# ads-b.net
KiCad netlist of a schematic drawn in EAGLE
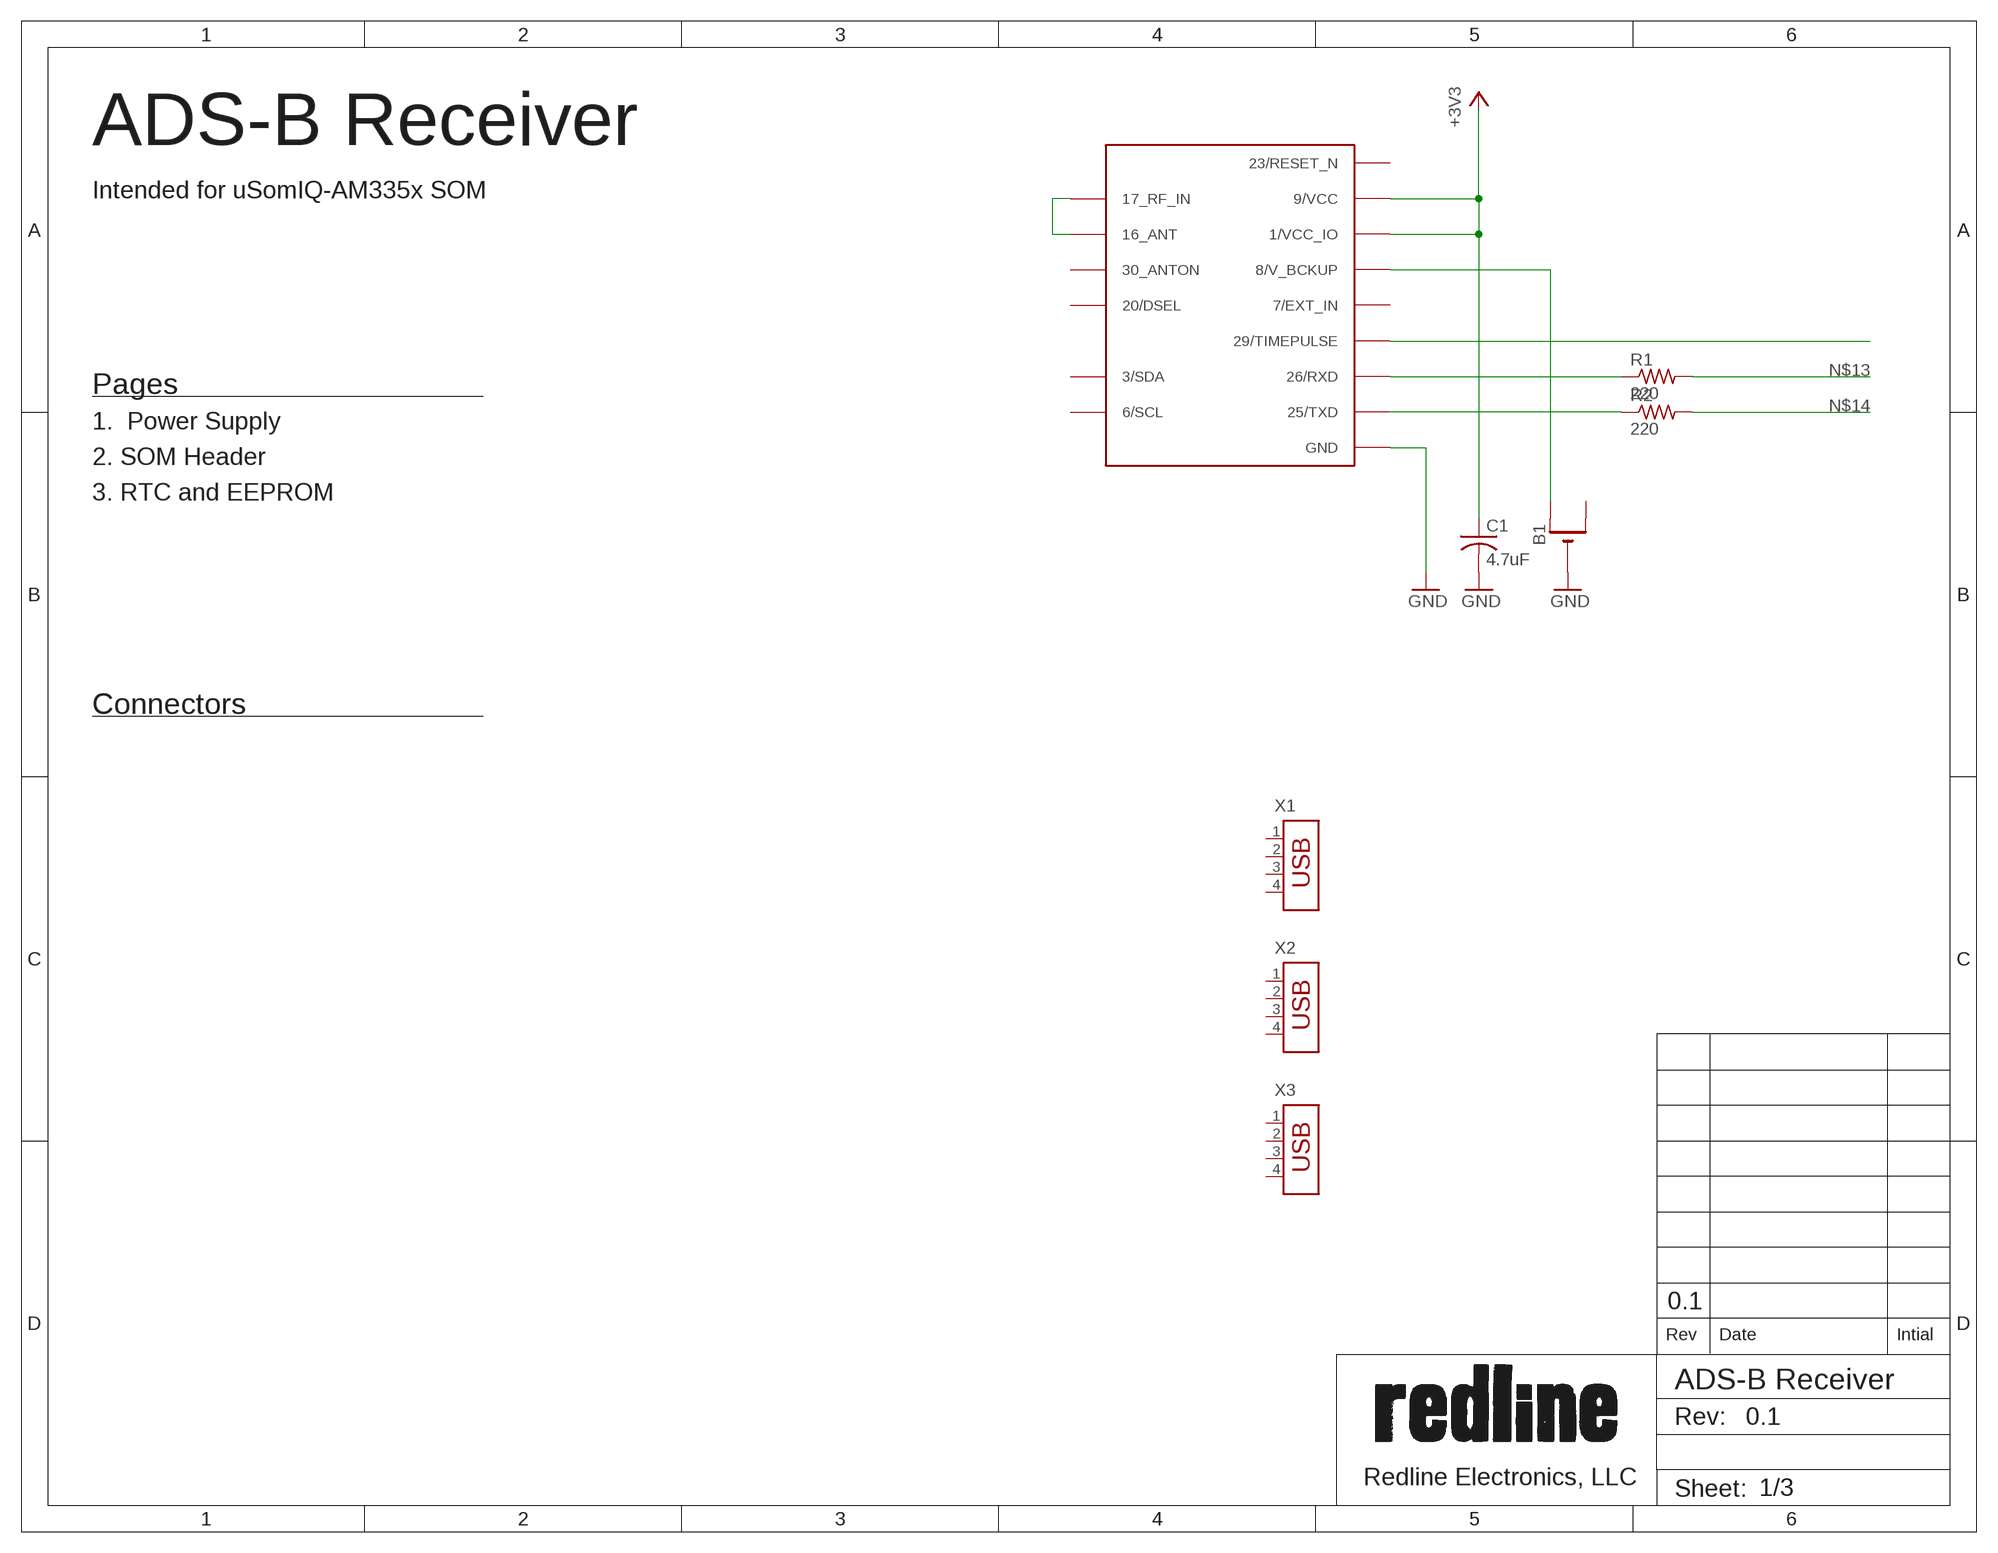
[diagram p0: schematic, sheet 1]
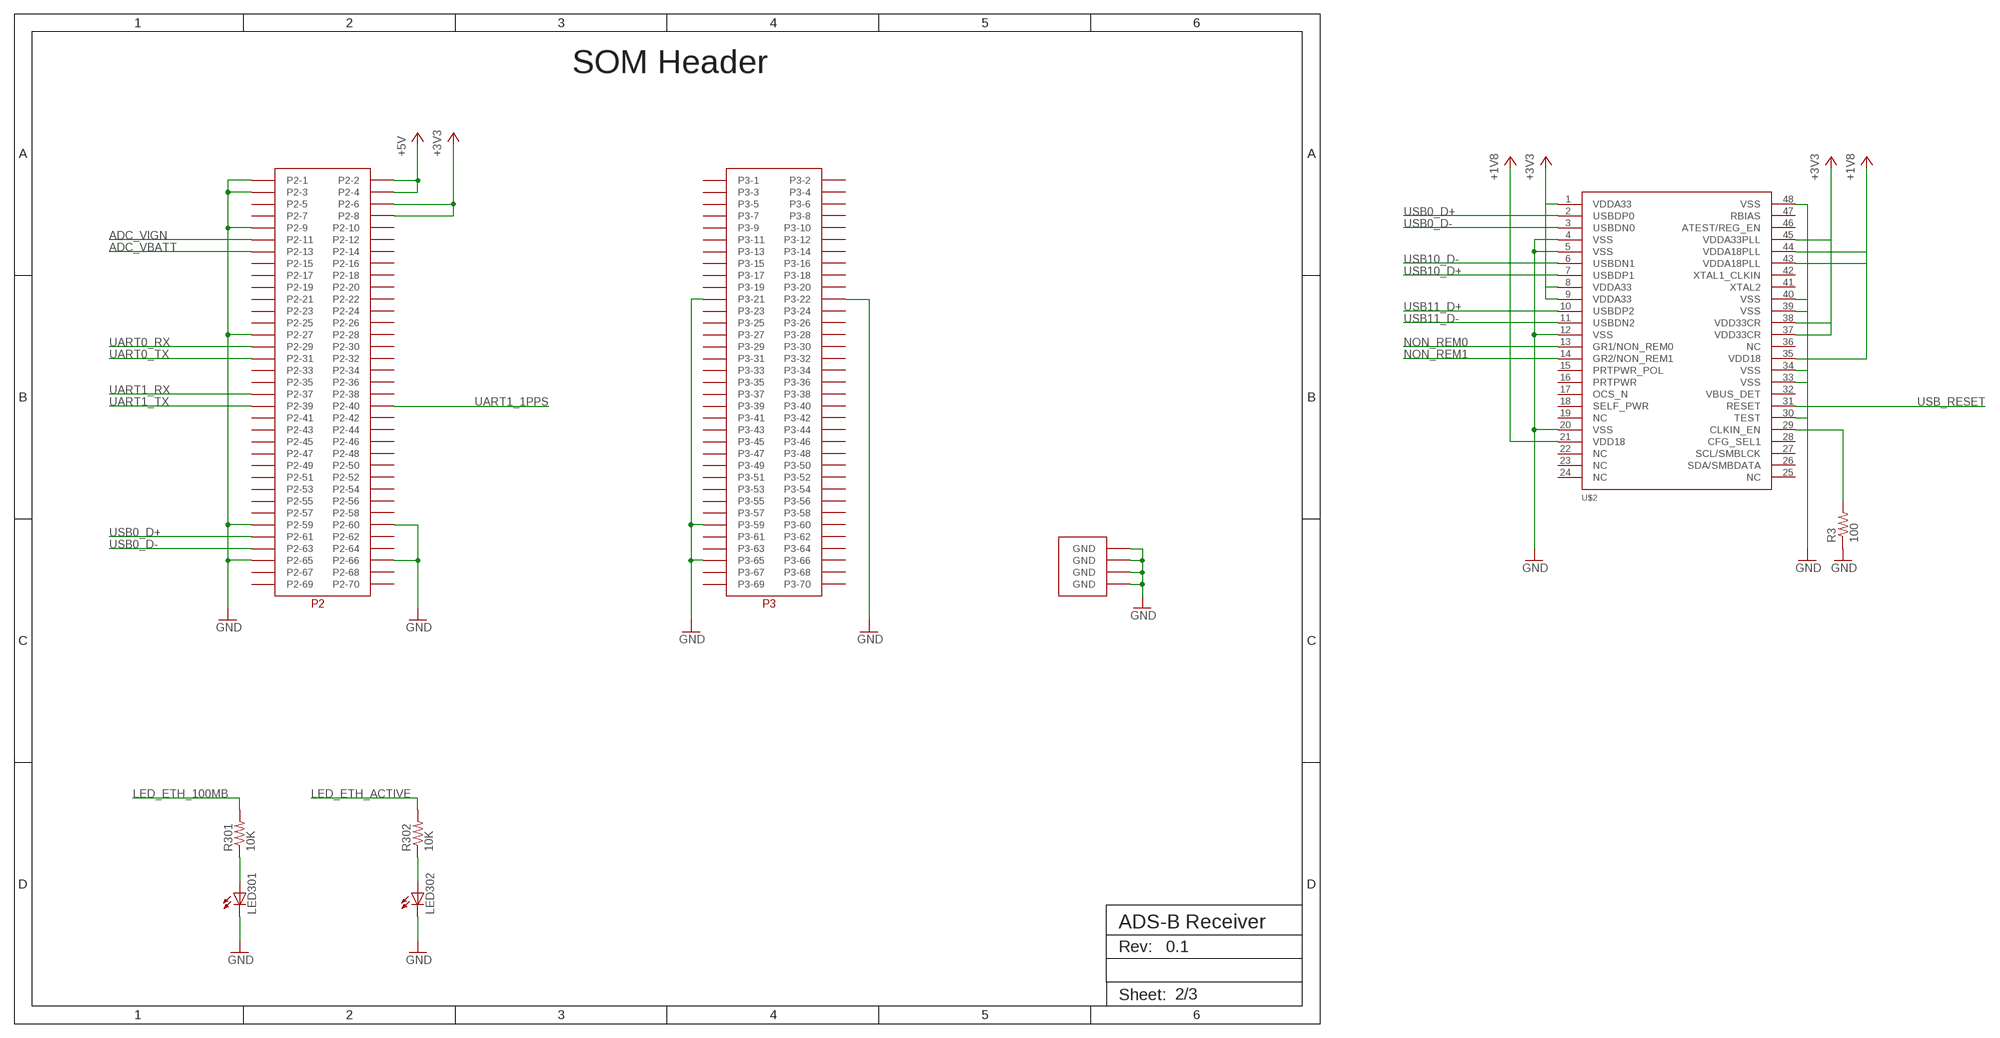
[diagram p1: schematic, sheet 2]
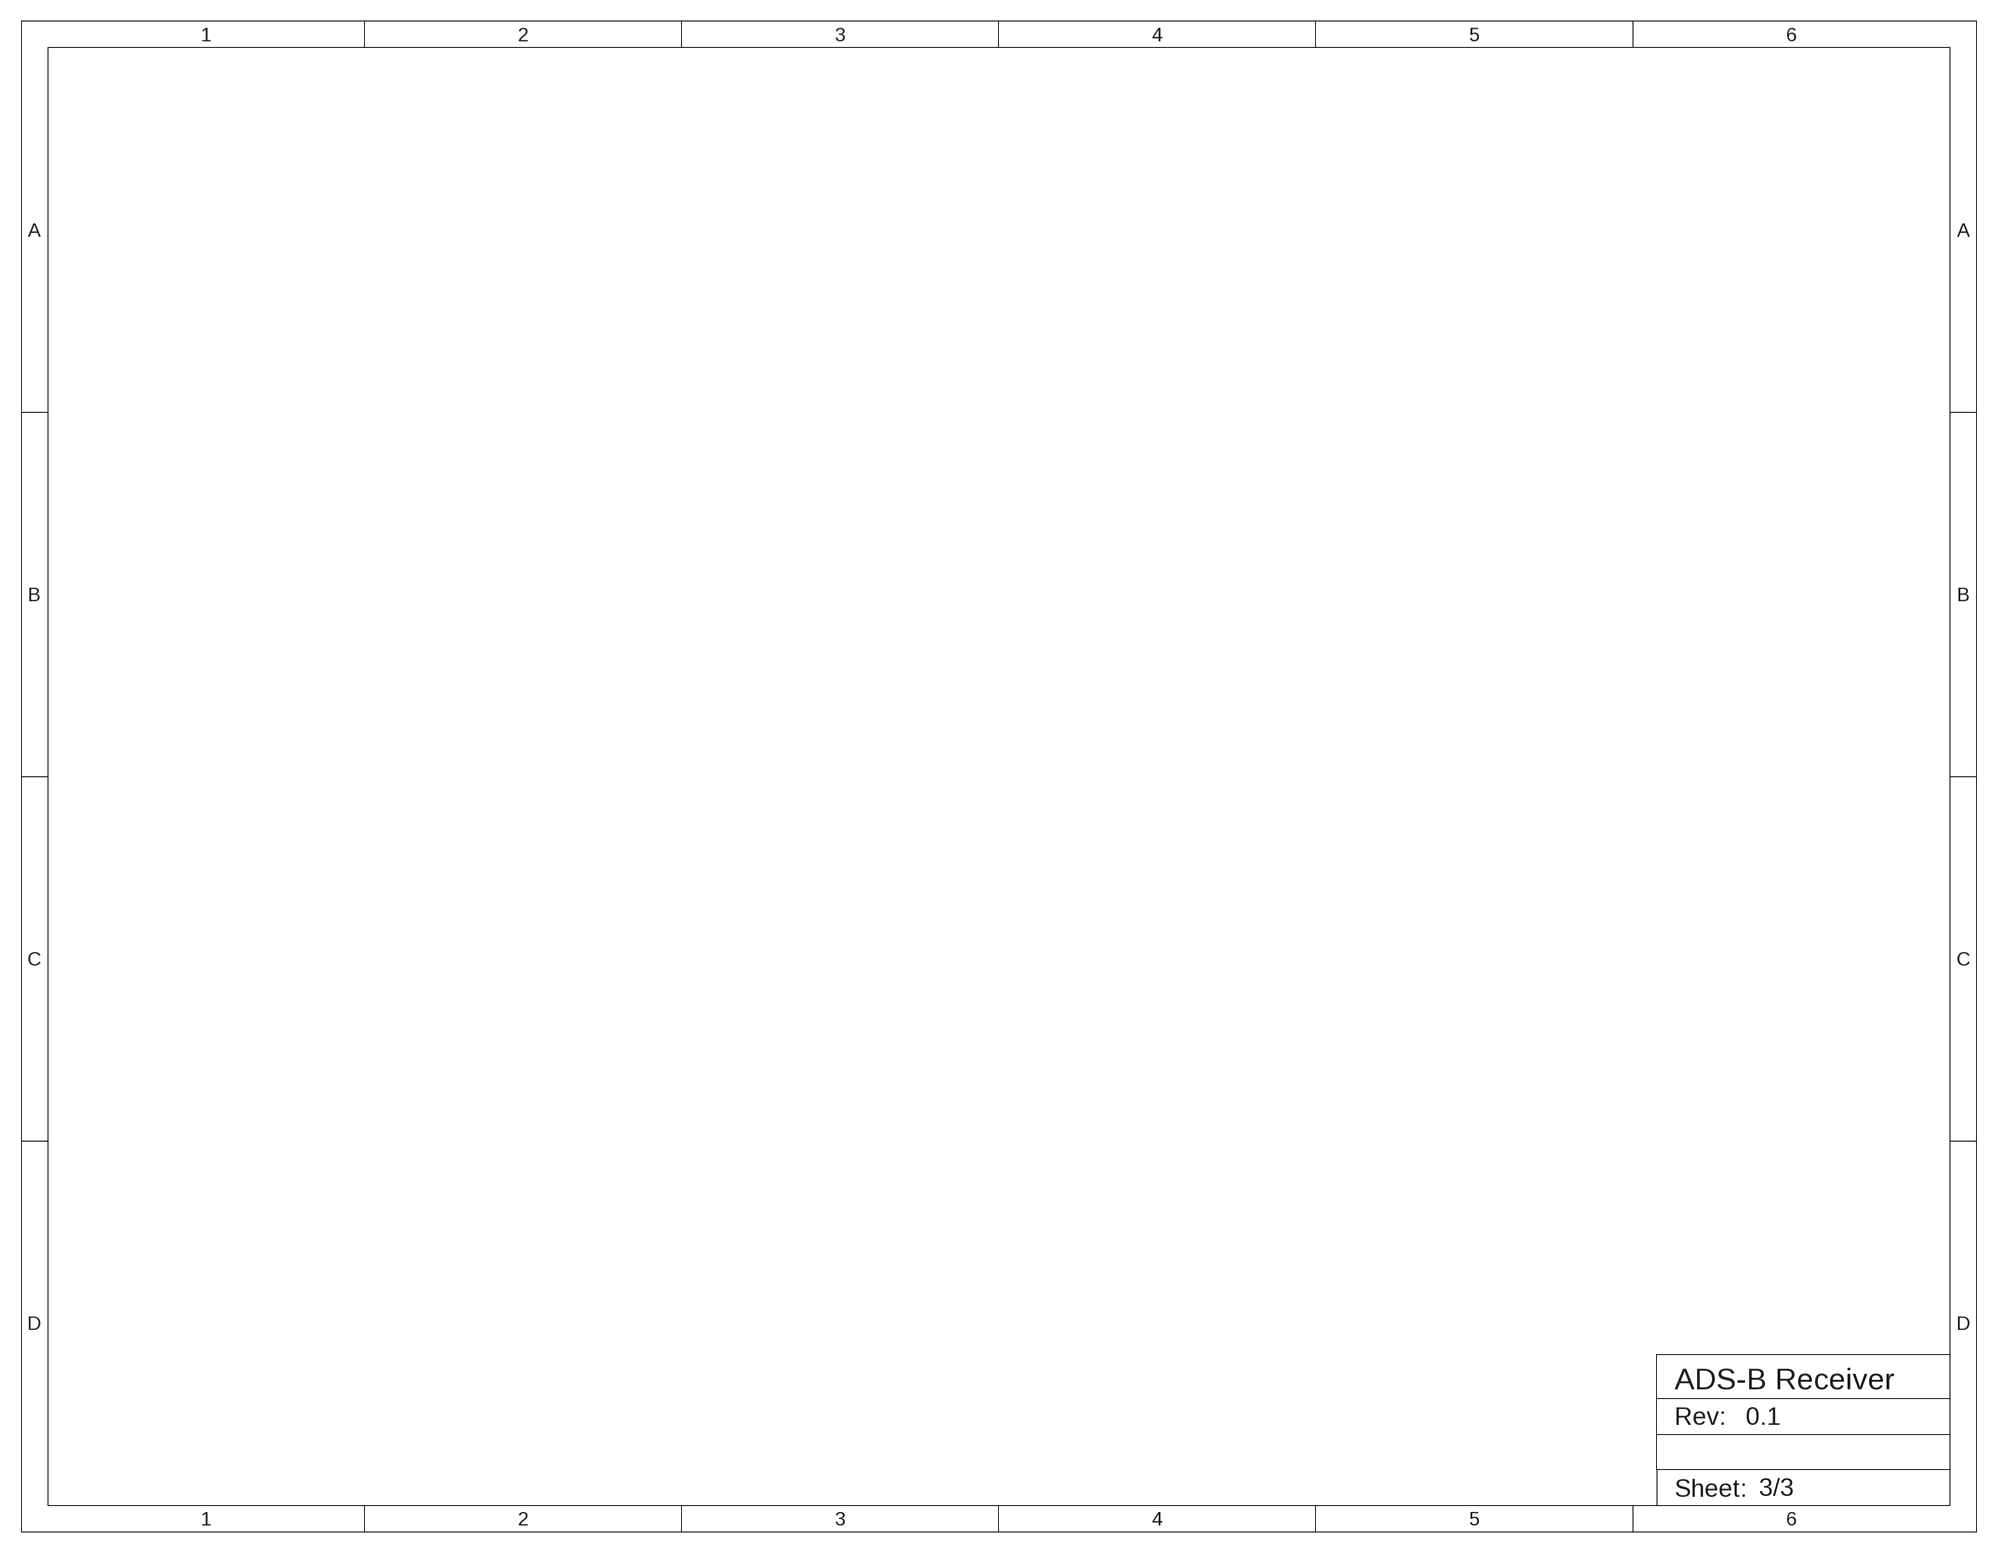
[diagram p2: schematic, sheet 3]

(export (version "E")
  (design (tool "Eeschema 10.0.6"))
  (components
    (comp (ref "LED301")
      (value "LEDSML0603")
      (footprint "eagle-import:SML0603")
      (libsource (lib "eagle-import") (part "LEDSML0603"))
    )
    (comp (ref "LED302")
      (value "LEDSML0603")
      (footprint "eagle-import:SML0603")
      (libsource (lib "eagle-import") (part "LEDSML0603"))
    )
    (comp (ref "P301")
      (value "USOMIQ-AM335X")
      (footprint "eagle-import:USOMIQ-AM335X")
      (libsource (lib "eagle-import") (part "USOMIQ-AM335X"))
    )
    (comp (ref "R3")
      (value "100")
      (footprint "eagle-import:R0603")
      (libsource (lib "eagle-import") (part "R-US_R0603"))
    )
    (comp (ref "R301")
      (value "10K")
      (footprint "eagle-import:R0603")
      (libsource (lib "eagle-import") (part "R-US_R0603"))
    )
    (comp (ref "R302")
      (value "10K")
      (footprint "eagle-import:R0603")
      (libsource (lib "eagle-import") (part "R-US_R0603"))
    )
    (comp (ref "U$2")
      (value "USB2502")
      (footprint "eagle-import:S-PQFP-G48")
      (libsource (lib "eagle-import") (part "USB2502"))
    )
    (comp (ref "B1")
      (value "CR1220SMT")
      (footprint "eagle-import:CR1220-SMD")
      (libsource (lib "eagle-import") (part "CR1220SMT"))
    )
    (comp (ref "C1")
      (value "4.7uF")
      (footprint "eagle-import:C0603")
      (libsource (lib "eagle-import") (part "C-USC0603"))
    )
    (comp (ref "R1")
      (value "220")
      (footprint "eagle-import:R0603")
      (libsource (lib "eagle-import") (part "R-US_R0603"))
    )
    (comp (ref "R2")
      (value "220")
      (footprint "eagle-import:R0603")
      (libsource (lib "eagle-import") (part "R-US_R0603"))
    )
    (comp (ref "U$1")
      (value "UBLOX_CAM")
      (footprint "eagle-import:UBLOX_CAM")
      (libsource (lib "eagle-import") (part "UBLOX_CAM"))
    )
    (comp (ref "X1")
      (value "USB-787616")
      (footprint "eagle-import:USB")
      (libsource (lib "eagle-import") (part "USB-787616"))
    )
    (comp (ref "X2")
      (value "USB-787616")
      (footprint "eagle-import:USB")
      (libsource (lib "eagle-import") (part "USB-787616"))
    )
    (comp (ref "X3")
      (value "USB-787616")
      (footprint "eagle-import:USB")
      (libsource (lib "eagle-import") (part "USB-787616"))
    )
  )
  (nets
    (net (code "1") (name "+3V3") (class "Default")
      (node (ref "C1") (pin "1") (pinfunction "1_1") (pintype "passive"))
      (node (ref "P301") (pin "P$6") (pinfunction "P2-6_P$6") (pintype "bidirectional"))
      (node (ref "P301") (pin "P$8") (pinfunction "P2-8_P$8") (pintype "bidirectional"))
      (node (ref "U$1") (pin "1/VCC_IO") (pinfunction "1/VCC_IO_1/VCC_IO") (pintype "power_in"))
      (node (ref "U$1") (pin "9/VCC") (pinfunction "9/VCC_9/VCC") (pintype "power_in"))
      (node (ref "U$2") (pin "1") (pinfunction "VDDA33_1") (pintype "bidirectional"))
      (node (ref "U$2") (pin "21") (pinfunction "VDD18_21") (pintype "bidirectional"))
      (node (ref "U$2") (pin "35") (pinfunction "VDD18_35") (pintype "bidirectional"))
      (node (ref "U$2") (pin "37") (pinfunction "VDD33CR_37") (pintype "bidirectional"))
      (node (ref "U$2") (pin "38") (pinfunction "VDD33CR_38") (pintype "bidirectional"))
      (node (ref "U$2") (pin "43") (pinfunction "VDDA18PLL_43") (pintype "bidirectional"))
      (node (ref "U$2") (pin "44") (pinfunction "VDDA18PLL_44") (pintype "bidirectional"))
      (node (ref "U$2") (pin "45") (pinfunction "VDDA33PLL_45") (pintype "bidirectional"))
      (node (ref "U$2") (pin "8") (pinfunction "VDDA33_8") (pintype "bidirectional"))
      (node (ref "U$2") (pin "9") (pinfunction "VDDA33_9") (pintype "bidirectional"))
    )
    (net (code "2") (name "+5V") (class "Default")
      (node (ref "P301") (pin "P$2") (pinfunction "P2-2_P$2") (pintype "bidirectional"))
      (node (ref "P301") (pin "P$4") (pinfunction "P2-4_P$4") (pintype "bidirectional"))
    )
    (net (code "3") (name "23{slash}RESET_N") (class "Default")
      (node (ref "U$1") (pin "23/RESET_N") (pinfunction "23/RESET_N_23/RESET_N") (pintype "power_in"))
    )
    (net (code "4") (name "ADC_VBATT") (class "Default")
      (node (ref "P301") (pin "P$13") (pinfunction "P2-13_P$13") (pintype "bidirectional"))
    )
    (net (code "5") (name "ADC_VIGN") (class "Default")
      (node (ref "P301") (pin "P$11") (pinfunction "P2-11_P$11") (pintype "bidirectional"))
    )
    (net (code "6") (name "GND") (class "Default")
      (node (ref "B1") (pin "-") (pinfunction "-_-") (pintype "passive"))
      (node (ref "C1") (pin "2") (pinfunction "2_2") (pintype "passive"))
      (node (ref "LED301") (pin "C") (pinfunction "C_C") (pintype "passive"))
      (node (ref "LED302") (pin "C") (pinfunction "C_C") (pintype "passive"))
      (node (ref "P301") (pin "MOUNT@0") (pinfunction "GND_MOUNT@0") (pintype "bidirectional"))
      (node (ref "P301") (pin "MOUNT@1") (pinfunction "GND_MOUNT@1") (pintype "bidirectional"))
      (node (ref "P301") (pin "MOUNT@2") (pinfunction "GND_MOUNT@2") (pintype "bidirectional"))
      (node (ref "P301") (pin "MOUNT@3") (pinfunction "GND_MOUNT@3") (pintype "bidirectional"))
      (node (ref "P301") (pin "P$1") (pinfunction "P2-1_P$1") (pintype "bidirectional"))
      (node (ref "P301") (pin "P$129") (pinfunction "P3-59_P$129") (pintype "bidirectional"))
      (node (ref "P301") (pin "P$135") (pinfunction "P3-65_P$135") (pintype "bidirectional"))
      (node (ref "P301") (pin "P$27") (pinfunction "P2-27_P$27") (pintype "bidirectional"))
      (node (ref "P301") (pin "P$3") (pinfunction "P2-3_P$3") (pintype "bidirectional"))
      (node (ref "P301") (pin "P$59") (pinfunction "P2-59_P$59") (pintype "bidirectional"))
      (node (ref "P301") (pin "P$60") (pinfunction "P2-60_P$60") (pintype "bidirectional"))
      (node (ref "P301") (pin "P$65") (pinfunction "P2-65_P$65") (pintype "bidirectional"))
      (node (ref "P301") (pin "P$66") (pinfunction "P2-66_P$66") (pintype "bidirectional"))
      (node (ref "P301") (pin "P$9") (pinfunction "P2-9_P$9") (pintype "bidirectional"))
      (node (ref "P301") (pin "P$91") (pinfunction "P3-21_P$91") (pintype "bidirectional"))
      (node (ref "P301") (pin "P$92") (pinfunction "P3-22_P$92") (pintype "bidirectional"))
      (node (ref "R3") (pin "1") (pinfunction "1_1") (pintype "passive"))
      (node (ref "U$1") (pin "10/GND") (pinfunction "GND_10/GND") (pintype "power_in"))
      (node (ref "U$1") (pin "11/GND") (pinfunction "GND_11/GND") (pintype "power_in"))
      (node (ref "U$1") (pin "12/GND") (pinfunction "GND_12/GND") (pintype "power_in"))
      (node (ref "U$1") (pin "13/GND") (pinfunction "GND_13/GND") (pintype "power_in"))
      (node (ref "U$1") (pin "14/GND") (pinfunction "GND_14/GND") (pintype "power_in"))
      (node (ref "U$1") (pin "15/GND") (pinfunction "GND_15/GND") (pintype "power_in"))
      (node (ref "U$1") (pin "18/GND") (pinfunction "GND_18/GND") (pintype "power_in"))
      (node (ref "U$1") (pin "19/GND") (pinfunction "GND_19/GND") (pintype "power_in"))
      (node (ref "U$1") (pin "21/GND") (pinfunction "GND_21/GND") (pintype "power_in"))
      (node (ref "U$1") (pin "22/GND") (pinfunction "GND_22/GND") (pintype "power_in"))
      (node (ref "U$1") (pin "27/GND") (pinfunction "GND_27/GND") (pintype "power_in"))
      (node (ref "U$1") (pin "31/GND") (pinfunction "GND_31/GND") (pintype "power_in"))
      (node (ref "U$1") (pin "4/GND") (pinfunction "GND_4/GND") (pintype "power_in"))
      (node (ref "U$1") (pin "5/GND") (pinfunction "GND_5/GND") (pintype "power_in"))
      (node (ref "U$2") (pin "12") (pinfunction "VSS_12") (pintype "bidirectional"))
      (node (ref "U$2") (pin "20") (pinfunction "VSS_20") (pintype "bidirectional"))
      (node (ref "U$2") (pin "30") (pinfunction "TEST_30") (pintype "bidirectional"))
      (node (ref "U$2") (pin "33") (pinfunction "VSS_33") (pintype "bidirectional"))
      (node (ref "U$2") (pin "34") (pinfunction "VSS_34") (pintype "bidirectional"))
      (node (ref "U$2") (pin "39") (pinfunction "VSS_39") (pintype "bidirectional"))
      (node (ref "U$2") (pin "4") (pinfunction "VSS_4") (pintype "bidirectional"))
      (node (ref "U$2") (pin "40") (pinfunction "VSS_40") (pintype "bidirectional"))
      (node (ref "U$2") (pin "48") (pinfunction "VSS_48") (pintype "bidirectional"))
      (node (ref "U$2") (pin "5") (pinfunction "VSS_5") (pintype "bidirectional"))
    )
    (net (code "7") (name "LED_ETH_100MB") (class "Default")
      (node (ref "R301") (pin "2") (pinfunction "2_2") (pintype "passive"))
    )
    (net (code "8") (name "LED_ETH_ACTIVE") (class "Default")
      (node (ref "R302") (pin "2") (pinfunction "2_2") (pintype "passive"))
    )
    (net (code "9") (name "N$13") (class "Default")
      (node (ref "R1") (pin "2") (pinfunction "2_2") (pintype "passive"))
    )
    (net (code "10") (name "N$14") (class "Default")
      (node (ref "R2") (pin "2") (pinfunction "2_2") (pintype "passive"))
    )
    (net (code "11") (name "NON_REM0") (class "Default")
      (node (ref "U$2") (pin "13") (pinfunction "GR1/NON_REM0_13") (pintype "bidirectional"))
    )
    (net (code "12") (name "NON_REM1") (class "Default")
      (node (ref "U$2") (pin "14") (pinfunction "GR2/NON_REM1_14") (pintype "bidirectional"))
    )
    (net (code "13") (name "Net-(B1-+)") (class "Default")
      (node (ref "B1") (pin "+$1") (pinfunction "+_+$1") (pintype "passive"))
      (node (ref "U$1") (pin "8/V_BCKP") (pinfunction "8/V_BCKUP_8/V_BCKP") (pintype "bidirectional"))
    )
    (net (code "14") (name "Net-(LED301-PadA)") (class "Default")
      (node (ref "LED301") (pin "A") (pinfunction "A_A") (pintype "passive"))
      (node (ref "R301") (pin "1") (pinfunction "1_1") (pintype "passive"))
    )
    (net (code "15") (name "Net-(LED302-PadA)") (class "Default")
      (node (ref "LED302") (pin "A") (pinfunction "A_A") (pintype "passive"))
      (node (ref "R302") (pin "1") (pinfunction "1_1") (pintype "passive"))
    )
    (net (code "16") (name "Net-(R1-Pad1)") (class "Default")
      (node (ref "R1") (pin "1") (pinfunction "1_1") (pintype "passive"))
      (node (ref "U$1") (pin "26/RXD") (pinfunction "26/RXD_26/RXD") (pintype "bidirectional"))
    )
    (net (code "17") (name "Net-(R2-Pad1)") (class "Default")
      (node (ref "R2") (pin "1") (pinfunction "1_1") (pintype "passive"))
      (node (ref "U$1") (pin "25/TXD") (pinfunction "25/TXD_25/TXD") (pintype "bidirectional"))
    )
    (net (code "18") (name "Net-(U$1-16_ANT)") (class "Default")
      (node (ref "U$1") (pin "16/ANT") (pinfunction "16_ANT_16/ANT") (pintype "power_in"))
      (node (ref "U$1") (pin "17/RF_IN") (pinfunction "17_RF_IN_17/RF_IN") (pintype "bidirectional"))
    )
    (net (code "19") (name "Net-(U$2-CLKIN_EN)") (class "Default")
      (node (ref "R3") (pin "2") (pinfunction "2_2") (pintype "passive"))
      (node (ref "U$2") (pin "29") (pinfunction "CLKIN_EN_29") (pintype "bidirectional"))
    )
    (net (code "20") (name "UART0_RX") (class "Default")
      (node (ref "P301") (pin "P$29") (pinfunction "P2-29_P$29") (pintype "bidirectional"))
    )
    (net (code "21") (name "UART0_TX") (class "Default")
      (node (ref "P301") (pin "P$31") (pinfunction "P2-31_P$31") (pintype "bidirectional"))
    )
    (net (code "22") (name "UART1_1PPS") (class "Default")
      (node (ref "P301") (pin "P$40") (pinfunction "P2-40_P$40") (pintype "bidirectional"))
    )
    (net (code "23") (name "UART1_RX") (class "Default")
      (node (ref "P301") (pin "P$37") (pinfunction "P2-37_P$37") (pintype "bidirectional"))
    )
    (net (code "24") (name "UART1_TX") (class "Default")
      (node (ref "P301") (pin "P$39") (pinfunction "P2-39_P$39") (pintype "bidirectional"))
    )
    (net (code "25") (name "USB0_D+") (class "Default")
      (node (ref "P301") (pin "P$61") (pinfunction "P2-61_P$61") (pintype "bidirectional"))
      (node (ref "U$2") (pin "2") (pinfunction "USBDP0_2") (pintype "bidirectional"))
    )
    (net (code "26") (name "USB0_D-") (class "Default")
      (node (ref "P301") (pin "P$63") (pinfunction "P2-63_P$63") (pintype "bidirectional"))
      (node (ref "U$2") (pin "3") (pinfunction "USBDN0_3") (pintype "bidirectional"))
    )
    (net (code "27") (name "USB10_D+") (class "Default")
      (node (ref "U$2") (pin "7") (pinfunction "USBDP1_7") (pintype "bidirectional"))
    )
    (net (code "28") (name "USB10_D-") (class "Default")
      (node (ref "U$2") (pin "6") (pinfunction "USBDN1_6") (pintype "bidirectional"))
    )
    (net (code "29") (name "USB11_D+") (class "Default")
      (node (ref "U$2") (pin "10") (pinfunction "USBDP2_10") (pintype "bidirectional"))
    )
    (net (code "30") (name "USB11_D-") (class "Default")
      (node (ref "U$2") (pin "11") (pinfunction "USBDN2_11") (pintype "bidirectional"))
    )
    (net (code "31") (name "USB_RESET") (class "Default")
      (node (ref "U$2") (pin "31") (pinfunction "RESET_31") (pintype "bidirectional"))
    )
    (net (code "32") (name "unconnected-(B1-+1-Pad+$2)") (class "Default")
      (node (ref "B1") (pin "+$2") (pinfunction "+1_+$2") (pintype "passive"))
    )
    (net (code "33") (name "unconnected-(P301-P2-5-PadP$5)") (class "Default")
      (node (ref "P301") (pin "P$5") (pinfunction "P2-5_P$5") (pintype "bidirectional"))
    )
    (net (code "34") (name "unconnected-(P301-P2-7-PadP$7)") (class "Default")
      (node (ref "P301") (pin "P$7") (pinfunction "P2-7_P$7") (pintype "bidirectional"))
    )
    (net (code "35") (name "unconnected-(P301-P2-10-PadP$10)") (class "Default")
      (node (ref "P301") (pin "P$10") (pinfunction "P2-10_P$10") (pintype "bidirectional"))
    )
    (net (code "36") (name "unconnected-(P301-P2-12-PadP$12)") (class "Default")
      (node (ref "P301") (pin "P$12") (pinfunction "P2-12_P$12") (pintype "bidirectional"))
    )
    (net (code "37") (name "unconnected-(P301-P2-14-PadP$14)") (class "Default")
      (node (ref "P301") (pin "P$14") (pinfunction "P2-14_P$14") (pintype "bidirectional"))
    )
    (net (code "38") (name "unconnected-(P301-P2-15-PadP$15)") (class "Default")
      (node (ref "P301") (pin "P$15") (pinfunction "P2-15_P$15") (pintype "bidirectional"))
    )
    (net (code "39") (name "unconnected-(P301-P2-16-PadP$16)") (class "Default")
      (node (ref "P301") (pin "P$16") (pinfunction "P2-16_P$16") (pintype "bidirectional"))
    )
    (net (code "40") (name "unconnected-(P301-P2-17-PadP$17)") (class "Default")
      (node (ref "P301") (pin "P$17") (pinfunction "P2-17_P$17") (pintype "bidirectional"))
    )
    (net (code "41") (name "unconnected-(P301-P2-18-PadP$18)") (class "Default")
      (node (ref "P301") (pin "P$18") (pinfunction "P2-18_P$18") (pintype "bidirectional"))
    )
    (net (code "42") (name "unconnected-(P301-P2-19-PadP$19)") (class "Default")
      (node (ref "P301") (pin "P$19") (pinfunction "P2-19_P$19") (pintype "bidirectional"))
    )
    (net (code "43") (name "unconnected-(P301-P2-20-PadP$20)") (class "Default")
      (node (ref "P301") (pin "P$20") (pinfunction "P2-20_P$20") (pintype "bidirectional"))
    )
    (net (code "44") (name "unconnected-(P301-P2-21-PadP$21)") (class "Default")
      (node (ref "P301") (pin "P$21") (pinfunction "P2-21_P$21") (pintype "bidirectional"))
    )
    (net (code "45") (name "unconnected-(P301-P2-22-PadP$22)") (class "Default")
      (node (ref "P301") (pin "P$22") (pinfunction "P2-22_P$22") (pintype "bidirectional"))
    )
    (net (code "46") (name "unconnected-(P301-P2-23-PadP$23)") (class "Default")
      (node (ref "P301") (pin "P$23") (pinfunction "P2-23_P$23") (pintype "bidirectional"))
    )
    (net (code "47") (name "unconnected-(P301-P2-24-PadP$24)") (class "Default")
      (node (ref "P301") (pin "P$24") (pinfunction "P2-24_P$24") (pintype "bidirectional"))
    )
    (net (code "48") (name "unconnected-(P301-P2-25-PadP$25)") (class "Default")
      (node (ref "P301") (pin "P$25") (pinfunction "P2-25_P$25") (pintype "bidirectional"))
    )
    (net (code "49") (name "unconnected-(P301-P2-26-PadP$26)") (class "Default")
      (node (ref "P301") (pin "P$26") (pinfunction "P2-26_P$26") (pintype "bidirectional"))
    )
    (net (code "50") (name "unconnected-(P301-P2-28-PadP$28)") (class "Default")
      (node (ref "P301") (pin "P$28") (pinfunction "P2-28_P$28") (pintype "bidirectional"))
    )
    (net (code "51") (name "unconnected-(P301-P2-30-PadP$30)") (class "Default")
      (node (ref "P301") (pin "P$30") (pinfunction "P2-30_P$30") (pintype "bidirectional"))
    )
    (net (code "52") (name "unconnected-(P301-P2-32-PadP$32)") (class "Default")
      (node (ref "P301") (pin "P$32") (pinfunction "P2-32_P$32") (pintype "bidirectional"))
    )
    (net (code "53") (name "unconnected-(P301-P2-33-PadP$33)") (class "Default")
      (node (ref "P301") (pin "P$33") (pinfunction "P2-33_P$33") (pintype "bidirectional"))
    )
    (net (code "54") (name "unconnected-(P301-P2-34-PadP$34)") (class "Default")
      (node (ref "P301") (pin "P$34") (pinfunction "P2-34_P$34") (pintype "bidirectional"))
    )
    (net (code "55") (name "unconnected-(P301-P2-35-PadP$35)") (class "Default")
      (node (ref "P301") (pin "P$35") (pinfunction "P2-35_P$35") (pintype "bidirectional"))
    )
    (net (code "56") (name "unconnected-(P301-P2-36-PadP$36)") (class "Default")
      (node (ref "P301") (pin "P$36") (pinfunction "P2-36_P$36") (pintype "bidirectional"))
    )
    (net (code "57") (name "unconnected-(P301-P2-38-PadP$38)") (class "Default")
      (node (ref "P301") (pin "P$38") (pinfunction "P2-38_P$38") (pintype "bidirectional"))
    )
    (net (code "58") (name "unconnected-(P301-P2-41-PadP$41)") (class "Default")
      (node (ref "P301") (pin "P$41") (pinfunction "P2-41_P$41") (pintype "bidirectional"))
    )
    (net (code "59") (name "unconnected-(P301-P2-42-PadP$42)") (class "Default")
      (node (ref "P301") (pin "P$42") (pinfunction "P2-42_P$42") (pintype "bidirectional"))
    )
    (net (code "60") (name "unconnected-(P301-P2-43-PadP$43)") (class "Default")
      (node (ref "P301") (pin "P$43") (pinfunction "P2-43_P$43") (pintype "bidirectional"))
    )
    (net (code "61") (name "unconnected-(P301-P2-44-PadP$44)") (class "Default")
      (node (ref "P301") (pin "P$44") (pinfunction "P2-44_P$44") (pintype "bidirectional"))
    )
    (net (code "62") (name "unconnected-(P301-P2-45-PadP$45)") (class "Default")
      (node (ref "P301") (pin "P$45") (pinfunction "P2-45_P$45") (pintype "bidirectional"))
    )
    (net (code "63") (name "unconnected-(P301-P2-46-PadP$46)") (class "Default")
      (node (ref "P301") (pin "P$46") (pinfunction "P2-46_P$46") (pintype "bidirectional"))
    )
    (net (code "64") (name "unconnected-(P301-P2-47-PadP$47)") (class "Default")
      (node (ref "P301") (pin "P$47") (pinfunction "P2-47_P$47") (pintype "bidirectional"))
    )
    (net (code "65") (name "unconnected-(P301-P2-48-PadP$48)") (class "Default")
      (node (ref "P301") (pin "P$48") (pinfunction "P2-48_P$48") (pintype "bidirectional"))
    )
    (net (code "66") (name "unconnected-(P301-P2-49-PadP$49)") (class "Default")
      (node (ref "P301") (pin "P$49") (pinfunction "P2-49_P$49") (pintype "bidirectional"))
    )
    (net (code "67") (name "unconnected-(P301-P2-50-PadP$50)") (class "Default")
      (node (ref "P301") (pin "P$50") (pinfunction "P2-50_P$50") (pintype "bidirectional"))
    )
    (net (code "68") (name "unconnected-(P301-P2-51-PadP$51)") (class "Default")
      (node (ref "P301") (pin "P$51") (pinfunction "P2-51_P$51") (pintype "bidirectional"))
    )
    (net (code "69") (name "unconnected-(P301-P2-52-PadP$52)") (class "Default")
      (node (ref "P301") (pin "P$52") (pinfunction "P2-52_P$52") (pintype "bidirectional"))
    )
    (net (code "70") (name "unconnected-(P301-P2-53-PadP$53)") (class "Default")
      (node (ref "P301") (pin "P$53") (pinfunction "P2-53_P$53") (pintype "bidirectional"))
    )
    (net (code "71") (name "unconnected-(P301-P2-54-PadP$54)") (class "Default")
      (node (ref "P301") (pin "P$54") (pinfunction "P2-54_P$54") (pintype "bidirectional"))
    )
    (net (code "72") (name "unconnected-(P301-P2-55-PadP$55)") (class "Default")
      (node (ref "P301") (pin "P$55") (pinfunction "P2-55_P$55") (pintype "bidirectional"))
    )
    (net (code "73") (name "unconnected-(P301-P2-56-PadP$56)") (class "Default")
      (node (ref "P301") (pin "P$56") (pinfunction "P2-56_P$56") (pintype "bidirectional"))
    )
    (net (code "74") (name "unconnected-(P301-P2-57-PadP$57)") (class "Default")
      (node (ref "P301") (pin "P$57") (pinfunction "P2-57_P$57") (pintype "bidirectional"))
    )
    (net (code "75") (name "unconnected-(P301-P2-58-PadP$58)") (class "Default")
      (node (ref "P301") (pin "P$58") (pinfunction "P2-58_P$58") (pintype "bidirectional"))
    )
    (net (code "76") (name "unconnected-(P301-P2-62-PadP$62)") (class "Default")
      (node (ref "P301") (pin "P$62") (pinfunction "P2-62_P$62") (pintype "bidirectional"))
    )
    (net (code "77") (name "unconnected-(P301-P2-64-PadP$64)") (class "Default")
      (node (ref "P301") (pin "P$64") (pinfunction "P2-64_P$64") (pintype "bidirectional"))
    )
    (net (code "78") (name "unconnected-(P301-P2-67-PadP$67)") (class "Default")
      (node (ref "P301") (pin "P$67") (pinfunction "P2-67_P$67") (pintype "bidirectional"))
    )
    (net (code "79") (name "unconnected-(P301-P2-68-PadP$68)") (class "Default")
      (node (ref "P301") (pin "P$68") (pinfunction "P2-68_P$68") (pintype "bidirectional"))
    )
    (net (code "80") (name "unconnected-(P301-P2-69-PadP$69)") (class "Default")
      (node (ref "P301") (pin "P$69") (pinfunction "P2-69_P$69") (pintype "bidirectional"))
    )
    (net (code "81") (name "unconnected-(P301-P2-70-PadP$70)") (class "Default")
      (node (ref "P301") (pin "P$70") (pinfunction "P2-70_P$70") (pintype "bidirectional"))
    )
    (net (code "82") (name "unconnected-(P301-P3-1-PadP$71)") (class "Default")
      (node (ref "P301") (pin "P$71") (pinfunction "P3-1_P$71") (pintype "bidirectional"))
    )
    (net (code "83") (name "unconnected-(P301-P3-2-PadP$72)") (class "Default")
      (node (ref "P301") (pin "P$72") (pinfunction "P3-2_P$72") (pintype "bidirectional"))
    )
    (net (code "84") (name "unconnected-(P301-P3-3-PadP$73)") (class "Default")
      (node (ref "P301") (pin "P$73") (pinfunction "P3-3_P$73") (pintype "bidirectional"))
    )
    (net (code "85") (name "unconnected-(P301-P3-4-PadP$74)") (class "Default")
      (node (ref "P301") (pin "P$74") (pinfunction "P3-4_P$74") (pintype "bidirectional"))
    )
    (net (code "86") (name "unconnected-(P301-P3-5-PadP$75)") (class "Default")
      (node (ref "P301") (pin "P$75") (pinfunction "P3-5_P$75") (pintype "bidirectional"))
    )
    (net (code "87") (name "unconnected-(P301-P3-6-PadP$76)") (class "Default")
      (node (ref "P301") (pin "P$76") (pinfunction "P3-6_P$76") (pintype "bidirectional"))
    )
    (net (code "88") (name "unconnected-(P301-P3-7-PadP$77)") (class "Default")
      (node (ref "P301") (pin "P$77") (pinfunction "P3-7_P$77") (pintype "bidirectional"))
    )
    (net (code "89") (name "unconnected-(P301-P3-8-PadP$78)") (class "Default")
      (node (ref "P301") (pin "P$78") (pinfunction "P3-8_P$78") (pintype "bidirectional"))
    )
    (net (code "90") (name "unconnected-(P301-P3-9-PadP$79)") (class "Default")
      (node (ref "P301") (pin "P$79") (pinfunction "P3-9_P$79") (pintype "bidirectional"))
    )
    (net (code "91") (name "unconnected-(P301-P3-10-PadP$80)") (class "Default")
      (node (ref "P301") (pin "P$80") (pinfunction "P3-10_P$80") (pintype "bidirectional"))
    )
    (net (code "92") (name "unconnected-(P301-P3-11-PadP$81)") (class "Default")
      (node (ref "P301") (pin "P$81") (pinfunction "P3-11_P$81") (pintype "bidirectional"))
    )
    (net (code "93") (name "unconnected-(P301-P3-12-PadP$82)") (class "Default")
      (node (ref "P301") (pin "P$82") (pinfunction "P3-12_P$82") (pintype "bidirectional"))
    )
    (net (code "94") (name "unconnected-(P301-P3-13-PadP$83)") (class "Default")
      (node (ref "P301") (pin "P$83") (pinfunction "P3-13_P$83") (pintype "bidirectional"))
    )
    (net (code "95") (name "unconnected-(P301-P3-14-PadP$84)") (class "Default")
      (node (ref "P301") (pin "P$84") (pinfunction "P3-14_P$84") (pintype "bidirectional"))
    )
    (net (code "96") (name "unconnected-(P301-P3-15-PadP$85)") (class "Default")
      (node (ref "P301") (pin "P$85") (pinfunction "P3-15_P$85") (pintype "bidirectional"))
    )
    (net (code "97") (name "unconnected-(P301-P3-16-PadP$86)") (class "Default")
      (node (ref "P301") (pin "P$86") (pinfunction "P3-16_P$86") (pintype "bidirectional"))
    )
    (net (code "98") (name "unconnected-(P301-P3-17-PadP$87)") (class "Default")
      (node (ref "P301") (pin "P$87") (pinfunction "P3-17_P$87") (pintype "bidirectional"))
    )
    (net (code "99") (name "unconnected-(P301-P3-18-PadP$88)") (class "Default")
      (node (ref "P301") (pin "P$88") (pinfunction "P3-18_P$88") (pintype "bidirectional"))
    )
    (net (code "100") (name "unconnected-(P301-P3-19-PadP$89)") (class "Default")
      (node (ref "P301") (pin "P$89") (pinfunction "P3-19_P$89") (pintype "bidirectional"))
    )
    (net (code "101") (name "unconnected-(P301-P3-20-PadP$90)") (class "Default")
      (node (ref "P301") (pin "P$90") (pinfunction "P3-20_P$90") (pintype "bidirectional"))
    )
    (net (code "102") (name "unconnected-(P301-P3-23-PadP$93)") (class "Default")
      (node (ref "P301") (pin "P$93") (pinfunction "P3-23_P$93") (pintype "bidirectional"))
    )
    (net (code "103") (name "unconnected-(P301-P3-24-PadP$94)") (class "Default")
      (node (ref "P301") (pin "P$94") (pinfunction "P3-24_P$94") (pintype "bidirectional"))
    )
    (net (code "104") (name "unconnected-(P301-P3-25-PadP$95)") (class "Default")
      (node (ref "P301") (pin "P$95") (pinfunction "P3-25_P$95") (pintype "bidirectional"))
    )
    (net (code "105") (name "unconnected-(P301-P3-26-PadP$96)") (class "Default")
      (node (ref "P301") (pin "P$96") (pinfunction "P3-26_P$96") (pintype "bidirectional"))
    )
    (net (code "106") (name "unconnected-(P301-P3-27-PadP$97)") (class "Default")
      (node (ref "P301") (pin "P$97") (pinfunction "P3-27_P$97") (pintype "bidirectional"))
    )
    (net (code "107") (name "unconnected-(P301-P3-28-PadP$98)") (class "Default")
      (node (ref "P301") (pin "P$98") (pinfunction "P3-28_P$98") (pintype "bidirectional"))
    )
    (net (code "108") (name "unconnected-(P301-P3-29-PadP$99)") (class "Default")
      (node (ref "P301") (pin "P$99") (pinfunction "P3-29_P$99") (pintype "bidirectional"))
    )
    (net (code "109") (name "unconnected-(P301-P3-30-PadP$100)") (class "Default")
      (node (ref "P301") (pin "P$100") (pinfunction "P3-30_P$100") (pintype "bidirectional"))
    )
    (net (code "110") (name "unconnected-(P301-P3-31-PadP$101)") (class "Default")
      (node (ref "P301") (pin "P$101") (pinfunction "P3-31_P$101") (pintype "bidirectional"))
    )
    (net (code "111") (name "unconnected-(P301-P3-32-PadP$102)") (class "Default")
      (node (ref "P301") (pin "P$102") (pinfunction "P3-32_P$102") (pintype "bidirectional"))
    )
    (net (code "112") (name "unconnected-(P301-P3-33-PadP$103)") (class "Default")
      (node (ref "P301") (pin "P$103") (pinfunction "P3-33_P$103") (pintype "bidirectional"))
    )
    (net (code "113") (name "unconnected-(P301-P3-34-PadP$104)") (class "Default")
      (node (ref "P301") (pin "P$104") (pinfunction "P3-34_P$104") (pintype "bidirectional"))
    )
    (net (code "114") (name "unconnected-(P301-P3-35-PadP$105)") (class "Default")
      (node (ref "P301") (pin "P$105") (pinfunction "P3-35_P$105") (pintype "bidirectional"))
    )
    (net (code "115") (name "unconnected-(P301-P3-36-PadP$106)") (class "Default")
      (node (ref "P301") (pin "P$106") (pinfunction "P3-36_P$106") (pintype "bidirectional"))
    )
    (net (code "116") (name "unconnected-(P301-P3-37-PadP$107)") (class "Default")
      (node (ref "P301") (pin "P$107") (pinfunction "P3-37_P$107") (pintype "bidirectional"))
    )
    (net (code "117") (name "unconnected-(P301-P3-38-PadP$108)") (class "Default")
      (node (ref "P301") (pin "P$108") (pinfunction "P3-38_P$108") (pintype "bidirectional"))
    )
    (net (code "118") (name "unconnected-(P301-P3-39-PadP$109)") (class "Default")
      (node (ref "P301") (pin "P$109") (pinfunction "P3-39_P$109") (pintype "bidirectional"))
    )
    (net (code "119") (name "unconnected-(P301-P3-40-PadP$110)") (class "Default")
      (node (ref "P301") (pin "P$110") (pinfunction "P3-40_P$110") (pintype "bidirectional"))
    )
    (net (code "120") (name "unconnected-(P301-P3-41-PadP$111)") (class "Default")
      (node (ref "P301") (pin "P$111") (pinfunction "P3-41_P$111") (pintype "bidirectional"))
    )
    (net (code "121") (name "unconnected-(P301-P3-42-PadP$112)") (class "Default")
      (node (ref "P301") (pin "P$112") (pinfunction "P3-42_P$112") (pintype "bidirectional"))
    )
    (net (code "122") (name "unconnected-(P301-P3-43-PadP$113)") (class "Default")
      (node (ref "P301") (pin "P$113") (pinfunction "P3-43_P$113") (pintype "bidirectional"))
    )
    (net (code "123") (name "unconnected-(P301-P3-44-PadP$114)") (class "Default")
      (node (ref "P301") (pin "P$114") (pinfunction "P3-44_P$114") (pintype "bidirectional"))
    )
    (net (code "124") (name "unconnected-(P301-P3-45-PadP$115)") (class "Default")
      (node (ref "P301") (pin "P$115") (pinfunction "P3-45_P$115") (pintype "bidirectional"))
    )
    (net (code "125") (name "unconnected-(P301-P3-46-PadP$116)") (class "Default")
      (node (ref "P301") (pin "P$116") (pinfunction "P3-46_P$116") (pintype "bidirectional"))
    )
    (net (code "126") (name "unconnected-(P301-P3-47-PadP$117)") (class "Default")
      (node (ref "P301") (pin "P$117") (pinfunction "P3-47_P$117") (pintype "bidirectional"))
    )
    (net (code "127") (name "unconnected-(P301-P3-48-PadP$118)") (class "Default")
      (node (ref "P301") (pin "P$118") (pinfunction "P3-48_P$118") (pintype "bidirectional"))
    )
    (net (code "128") (name "unconnected-(P301-P3-49-PadP$119)") (class "Default")
      (node (ref "P301") (pin "P$119") (pinfunction "P3-49_P$119") (pintype "bidirectional"))
    )
    (net (code "129") (name "unconnected-(P301-P3-50-PadP$120)") (class "Default")
      (node (ref "P301") (pin "P$120") (pinfunction "P3-50_P$120") (pintype "bidirectional"))
    )
    (net (code "130") (name "unconnected-(P301-P3-51-PadP$121)") (class "Default")
      (node (ref "P301") (pin "P$121") (pinfunction "P3-51_P$121") (pintype "bidirectional"))
    )
    (net (code "131") (name "unconnected-(P301-P3-52-PadP$122)") (class "Default")
      (node (ref "P301") (pin "P$122") (pinfunction "P3-52_P$122") (pintype "bidirectional"))
    )
    (net (code "132") (name "unconnected-(P301-P3-53-PadP$123)") (class "Default")
      (node (ref "P301") (pin "P$123") (pinfunction "P3-53_P$123") (pintype "bidirectional"))
    )
    (net (code "133") (name "unconnected-(P301-P3-54-PadP$124)") (class "Default")
      (node (ref "P301") (pin "P$124") (pinfunction "P3-54_P$124") (pintype "bidirectional"))
    )
    (net (code "134") (name "unconnected-(P301-P3-55-PadP$125)") (class "Default")
      (node (ref "P301") (pin "P$125") (pinfunction "P3-55_P$125") (pintype "bidirectional"))
    )
    (net (code "135") (name "unconnected-(P301-P3-56-PadP$126)") (class "Default")
      (node (ref "P301") (pin "P$126") (pinfunction "P3-56_P$126") (pintype "bidirectional"))
    )
    (net (code "136") (name "unconnected-(P301-P3-57-PadP$127)") (class "Default")
      (node (ref "P301") (pin "P$127") (pinfunction "P3-57_P$127") (pintype "bidirectional"))
    )
    (net (code "137") (name "unconnected-(P301-P3-58-PadP$128)") (class "Default")
      (node (ref "P301") (pin "P$128") (pinfunction "P3-58_P$128") (pintype "bidirectional"))
    )
    (net (code "138") (name "unconnected-(P301-P3-60-PadP$130)") (class "Default")
      (node (ref "P301") (pin "P$130") (pinfunction "P3-60_P$130") (pintype "bidirectional"))
    )
    (net (code "139") (name "unconnected-(P301-P3-61-PadP$131)") (class "Default")
      (node (ref "P301") (pin "P$131") (pinfunction "P3-61_P$131") (pintype "bidirectional"))
    )
    (net (code "140") (name "unconnected-(P301-P3-62-PadP$132)") (class "Default")
      (node (ref "P301") (pin "P$132") (pinfunction "P3-62_P$132") (pintype "bidirectional"))
    )
    (net (code "141") (name "unconnected-(P301-P3-63-PadP$133)") (class "Default")
      (node (ref "P301") (pin "P$133") (pinfunction "P3-63_P$133") (pintype "bidirectional"))
    )
    (net (code "142") (name "unconnected-(P301-P3-64-PadP$134)") (class "Default")
      (node (ref "P301") (pin "P$134") (pinfunction "P3-64_P$134") (pintype "bidirectional"))
    )
    (net (code "143") (name "unconnected-(P301-P3-66-PadP$136)") (class "Default")
      (node (ref "P301") (pin "P$136") (pinfunction "P3-66_P$136") (pintype "bidirectional"))
    )
    (net (code "144") (name "unconnected-(P301-P3-67-PadP$137)") (class "Default")
      (node (ref "P301") (pin "P$137") (pinfunction "P3-67_P$137") (pintype "bidirectional"))
    )
    (net (code "145") (name "unconnected-(P301-P3-68-PadP$138)") (class "Default")
      (node (ref "P301") (pin "P$138") (pinfunction "P3-68_P$138") (pintype "bidirectional"))
    )
    (net (code "146") (name "unconnected-(P301-P3-69-PadP$139)") (class "Default")
      (node (ref "P301") (pin "P$139") (pinfunction "P3-69_P$139") (pintype "bidirectional"))
    )
    (net (code "147") (name "unconnected-(P301-P3-70-PadP$140)") (class "Default")
      (node (ref "P301") (pin "P$140") (pinfunction "P3-70_P$140") (pintype "bidirectional"))
    )
    (net (code "148") (name "unconnected-(U$1-7{slash}EXT_IN-Pad7{slash}EXINT)") (class "Default")
      (node (ref "U$1") (pin "7/EXINT") (pinfunction "7/EXT_IN_7/EXINT") (pintype "bidirectional"))
    )
    (net (code "149") (name "unconnected-(U$1-30_ANTON-Pad30{slash}ANTON)") (class "Default")
      (node (ref "U$1") (pin "30/ANTON") (pinfunction "30_ANTON_30/ANTON") (pintype "bidirectional"))
    )
    (net (code "150") (name "unconnected-(U$1-Pad3{slash}SDA)") (class "Default")
      (node (ref "U$1") (pin "3/SDA") (pinfunction "3/SDA_3/SDA") (pintype "bidirectional"))
    )
    (net (code "151") (name "unconnected-(U$1-Pad6{slash}SCL)") (class "Default")
      (node (ref "U$1") (pin "6/SCL") (pinfunction "6/SCL_6/SCL") (pintype "bidirectional"))
    )
    (net (code "152") (name "unconnected-(U$1-Pad20{slash}DSEL)") (class "Default")
      (node (ref "U$1") (pin "20/DSEL") (pinfunction "20/DSEL_20/DSEL") (pintype "bidirectional"))
    )
    (net (code "153") (name "unconnected-(U$1-Pad29{slash}TIMEPULSE)") (class "Default")
      (node (ref "U$1") (pin "29/TIMEPULSE") (pinfunction "29/TIMEPULSE_29/TIMEPULSE") (pintype "bidirectional"))
    )
    (net (code "154") (name "unconnected-(U$2-ATEST{slash}REG_EN-Pad46)") (class "Default")
      (node (ref "U$2") (pin "46") (pinfunction "ATEST/REG_EN_46") (pintype "bidirectional"))
    )
    (net (code "155") (name "unconnected-(U$2-CFG_SEL1-Pad28)") (class "Default")
      (node (ref "U$2") (pin "28") (pinfunction "CFG_SEL1_28") (pintype "bidirectional"))
    )
    (net (code "156") (name "unconnected-(U$2-NC-Pad19)") (class "Default")
      (node (ref "U$2") (pin "19") (pinfunction "NC_19") (pintype "bidirectional"))
    )
    (net (code "157") (name "unconnected-(U$2-NC-Pad22)") (class "Default")
      (node (ref "U$2") (pin "22") (pinfunction "NC_22") (pintype "bidirectional"))
    )
    (net (code "158") (name "unconnected-(U$2-NC-Pad23)") (class "Default")
      (node (ref "U$2") (pin "23") (pinfunction "NC_23") (pintype "bidirectional"))
    )
    (net (code "159") (name "unconnected-(U$2-NC-Pad24)") (class "Default")
      (node (ref "U$2") (pin "24") (pinfunction "NC_24") (pintype "bidirectional"))
    )
    (net (code "160") (name "unconnected-(U$2-NC-Pad25)") (class "Default")
      (node (ref "U$2") (pin "25") (pinfunction "NC_25") (pintype "bidirectional"))
    )
    (net (code "161") (name "unconnected-(U$2-NC-Pad36)") (class "Default")
      (node (ref "U$2") (pin "36") (pinfunction "NC_36") (pintype "bidirectional"))
    )
    (net (code "162") (name "unconnected-(U$2-OCS_N-Pad17)") (class "Default")
      (node (ref "U$2") (pin "17") (pinfunction "OCS_N_17") (pintype "bidirectional"))
    )
    (net (code "163") (name "unconnected-(U$2-PRTPWR-Pad16)") (class "Default")
      (node (ref "U$2") (pin "16") (pinfunction "PRTPWR_16") (pintype "bidirectional"))
    )
    (net (code "164") (name "unconnected-(U$2-PRTPWR_POL-Pad15)") (class "Default")
      (node (ref "U$2") (pin "15") (pinfunction "PRTPWR_POL_15") (pintype "bidirectional"))
    )
    (net (code "165") (name "unconnected-(U$2-RBIAS-Pad47)") (class "Default")
      (node (ref "U$2") (pin "47") (pinfunction "RBIAS_47") (pintype "bidirectional"))
    )
    (net (code "166") (name "unconnected-(U$2-SCL{slash}SMBLCK-Pad27)") (class "Default")
      (node (ref "U$2") (pin "27") (pinfunction "SCL/SMBLCK_27") (pintype "bidirectional"))
    )
    (net (code "167") (name "unconnected-(U$2-SDA{slash}SMBDATA-Pad26)") (class "Default")
      (node (ref "U$2") (pin "26") (pinfunction "SDA/SMBDATA_26") (pintype "bidirectional"))
    )
    (net (code "168") (name "unconnected-(U$2-SELF_PWR-Pad18)") (class "Default")
      (node (ref "U$2") (pin "18") (pinfunction "SELF_PWR_18") (pintype "bidirectional"))
    )
    (net (code "169") (name "unconnected-(U$2-VBUS_DET-Pad32)") (class "Default")
      (node (ref "U$2") (pin "32") (pinfunction "VBUS_DET_32") (pintype "bidirectional"))
    )
    (net (code "170") (name "unconnected-(U$2-XTAL1_CLKIN-Pad42)") (class "Default")
      (node (ref "U$2") (pin "42") (pinfunction "XTAL1_CLKIN_42") (pintype "bidirectional"))
    )
    (net (code "171") (name "unconnected-(U$2-XTAL2-Pad41)") (class "Default")
      (node (ref "U$2") (pin "41") (pinfunction "XTAL2_41") (pintype "bidirectional"))
    )
    (net (code "172") (name "unconnected-(X1-Pad1)") (class "Default")
      (node (ref "X1") (pin "1") (pinfunction "1_1") (pintype "passive"))
    )
    (net (code "173") (name "unconnected-(X1-Pad2)") (class "Default")
      (node (ref "X1") (pin "2") (pinfunction "2_2") (pintype "passive"))
    )
    (net (code "174") (name "unconnected-(X1-Pad3)") (class "Default")
      (node (ref "X1") (pin "3") (pinfunction "3_3") (pintype "passive"))
    )
    (net (code "175") (name "unconnected-(X1-Pad4)") (class "Default")
      (node (ref "X1") (pin "4") (pinfunction "4_4") (pintype "passive"))
    )
    (net (code "176") (name "unconnected-(X2-Pad1)") (class "Default")
      (node (ref "X2") (pin "1") (pinfunction "1_1") (pintype "passive"))
    )
    (net (code "177") (name "unconnected-(X2-Pad2)") (class "Default")
      (node (ref "X2") (pin "2") (pinfunction "2_2") (pintype "passive"))
    )
    (net (code "178") (name "unconnected-(X2-Pad3)") (class "Default")
      (node (ref "X2") (pin "3") (pinfunction "3_3") (pintype "passive"))
    )
    (net (code "179") (name "unconnected-(X2-Pad4)") (class "Default")
      (node (ref "X2") (pin "4") (pinfunction "4_4") (pintype "passive"))
    )
    (net (code "180") (name "unconnected-(X3-Pad1)") (class "Default")
      (node (ref "X3") (pin "1") (pinfunction "1_1") (pintype "passive"))
    )
    (net (code "181") (name "unconnected-(X3-Pad2)") (class "Default")
      (node (ref "X3") (pin "2") (pinfunction "2_2") (pintype "passive"))
    )
    (net (code "182") (name "unconnected-(X3-Pad3)") (class "Default")
      (node (ref "X3") (pin "3") (pinfunction "3_3") (pintype "passive"))
    )
    (net (code "183") (name "unconnected-(X3-Pad4)") (class "Default")
      (node (ref "X3") (pin "4") (pinfunction "4_4") (pintype "passive"))
    )
  )
)
